# Relayschematic.net
KiCad netlist of a schematic drawn in EAGLE
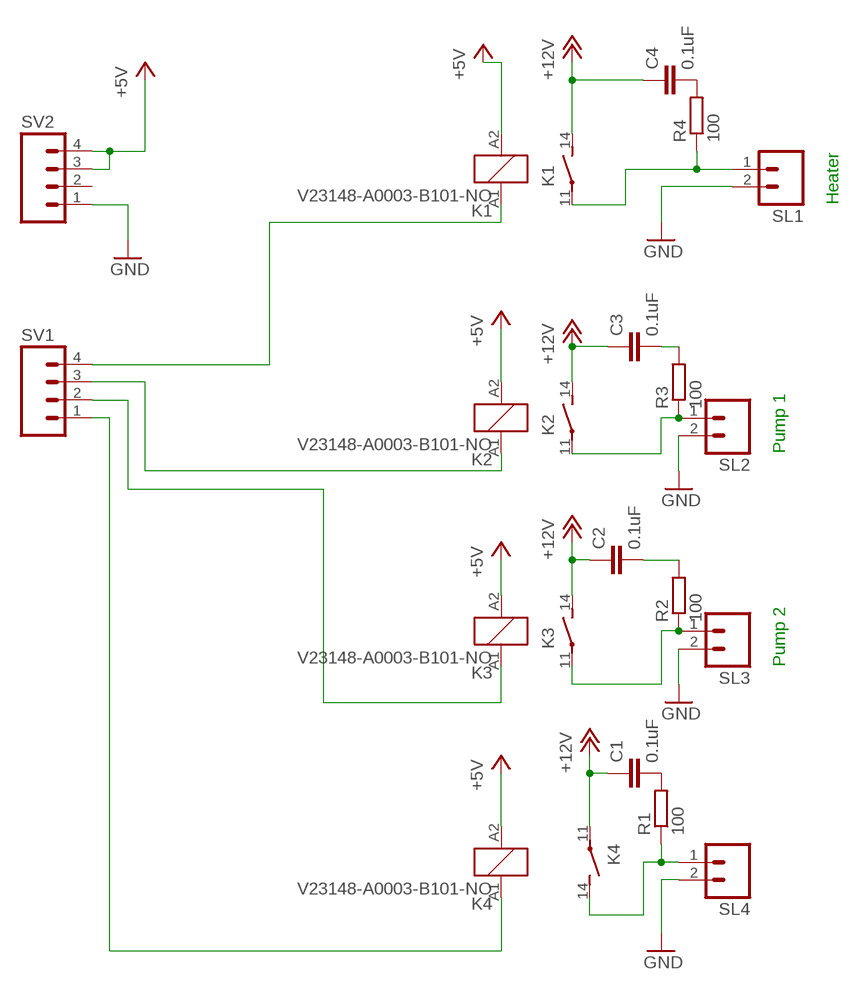
[diagram p0: schematic, sheet 1]

(export (version "E")
  (design (tool "Eeschema 10.0.6"))
  (components
    (comp (ref "C1")
      (value "0.1uF")
      (footprint "eagle-import:C5B2.5")
      (libsource (lib "eagle-import") (part "C5/2.5"))
    )
    (comp (ref "C2")
      (value "0.1uF")
      (footprint "eagle-import:C5B2.5")
      (libsource (lib "eagle-import") (part "C5/2.5"))
    )
    (comp (ref "C3")
      (value "0.1uF")
      (footprint "eagle-import:C5B2.5")
      (libsource (lib "eagle-import") (part "C5/2.5"))
    )
    (comp (ref "C4")
      (value "0.1uF")
      (footprint "eagle-import:C5B2.5")
      (libsource (lib "eagle-import") (part "C5/2.5"))
    )
    (comp (ref "K1")
      (value "V23148-A0003-B101-NO")
      (footprint "eagle-import:V23148-NO")
      (fields (field (name "MPN") "V23148-A0007-A101"))
      (libsource (lib "eagle-import") (part "V23148--NOA0003-B101"))
    )
    (comp (ref "K2")
      (value "V23148-A0003-B101-NO")
      (footprint "eagle-import:V23148-NO")
      (fields (field (name "MPN") "V23148-A0007-A101"))
      (libsource (lib "eagle-import") (part "V23148--NOA0003-B101"))
    )
    (comp (ref "K3")
      (value "V23148-A0003-B101-NO")
      (footprint "eagle-import:V23148-NO")
      (fields (field (name "MPN") "V23148-A0007-A101"))
      (libsource (lib "eagle-import") (part "V23148--NOA0003-B101"))
    )
    (comp (ref "K4")
      (value "V23148-A0003-B101-NO")
      (footprint "eagle-import:V23148-NO")
      (fields (field (name "MPN") "V23148-A0007-A101"))
      (libsource (lib "eagle-import") (part "V23148--NOA0003-B101"))
    )
    (comp (ref "R1")
      (value "100")
      (footprint "eagle-import:0207_10")
      (libsource (lib "eagle-import") (part "R-EU_0207/10"))
    )
    (comp (ref "R2")
      (value "100")
      (footprint "eagle-import:0207_10")
      (libsource (lib "eagle-import") (part "R-EU_0207/10"))
    )
    (comp (ref "R3")
      (value "100")
      (footprint "eagle-import:0207_10")
      (libsource (lib "eagle-import") (part "R-EU_0207/10"))
    )
    (comp (ref "R4")
      (value "100")
      (footprint "eagle-import:0207_10")
      (libsource (lib "eagle-import") (part "R-EU_0207/10"))
    )
    (comp (ref "SL1")
      (value "MA02")
      (footprint "eagle-import:02PA")
      (libsource (lib "eagle-import") (part "MA02"))
    )
    (comp (ref "SL2")
      (value "MA02")
      (footprint "eagle-import:02PA")
      (libsource (lib "eagle-import") (part "MA02"))
    )
    (comp (ref "SL3")
      (value "MA02")
      (footprint "eagle-import:02PA")
      (libsource (lib "eagle-import") (part "MA02"))
    )
    (comp (ref "SL4")
      (value "MA02")
      (footprint "eagle-import:02PA")
      (libsource (lib "eagle-import") (part "MA02"))
    )
    (comp (ref "SV1")
      (value "MA04")
      (footprint "eagle-import:04PA")
      (libsource (lib "eagle-import") (part "MA04"))
    )
    (comp (ref "SV2")
      (value "MA04")
      (footprint "eagle-import:04PA")
      (libsource (lib "eagle-import") (part "MA04"))
    )
  )
  (nets
    (net (code "1") (name "+5V") (class "Default")
      (node (ref "K1") (pin "A2") (pinfunction "2_A2") (pintype "passive"))
      (node (ref "K2") (pin "A2") (pinfunction "2_A2") (pintype "passive"))
      (node (ref "K3") (pin "A2") (pinfunction "2_A2") (pintype "passive"))
      (node (ref "K4") (pin "A2") (pinfunction "2_A2") (pintype "passive"))
      (node (ref "SV2") (pin "3") (pinfunction "3_3") (pintype "passive"))
      (node (ref "SV2") (pin "4") (pinfunction "4_4") (pintype "passive"))
    )
    (net (code "2") (name "+12V") (class "Default")
      (node (ref "C1") (pin "1") (pinfunction "1_1") (pintype "passive"))
      (node (ref "C2") (pin "1") (pinfunction "1_1") (pintype "passive"))
      (node (ref "C3") (pin "1") (pinfunction "1_1") (pintype "passive"))
      (node (ref "C4") (pin "1") (pinfunction "1_1") (pintype "passive"))
      (node (ref "K1") (pin "14") (pinfunction "S_14") (pintype "passive"))
      (node (ref "K2") (pin "14") (pinfunction "S_14") (pintype "passive"))
      (node (ref "K3") (pin "14") (pinfunction "S_14") (pintype "passive"))
      (node (ref "K4") (pin "11") (pinfunction "P_11") (pintype "passive"))
    )
    (net (code "3") (name "GND") (class "Default")
      (node (ref "SL1") (pin "2") (pinfunction "2_2") (pintype "passive"))
      (node (ref "SL2") (pin "2") (pinfunction "2_2") (pintype "passive"))
      (node (ref "SL3") (pin "2") (pinfunction "2_2") (pintype "passive"))
      (node (ref "SL4") (pin "2") (pinfunction "2_2") (pintype "passive"))
      (node (ref "SV2") (pin "1") (pinfunction "1_1") (pintype "passive"))
    )
    (net (code "4") (name "Net-(C1-Pad2)") (class "Default")
      (node (ref "C1") (pin "2") (pinfunction "2_2") (pintype "passive"))
      (node (ref "R1") (pin "2") (pinfunction "2_2") (pintype "passive"))
    )
    (net (code "5") (name "Net-(C2-Pad2)") (class "Default")
      (node (ref "C2") (pin "2") (pinfunction "2_2") (pintype "passive"))
      (node (ref "R2") (pin "2") (pinfunction "2_2") (pintype "passive"))
    )
    (net (code "6") (name "Net-(C3-Pad2)") (class "Default")
      (node (ref "C3") (pin "2") (pinfunction "2_2") (pintype "passive"))
      (node (ref "R3") (pin "2") (pinfunction "2_2") (pintype "passive"))
    )
    (net (code "7") (name "Net-(C4-Pad2)") (class "Default")
      (node (ref "C4") (pin "2") (pinfunction "2_2") (pintype "passive"))
      (node (ref "R4") (pin "2") (pinfunction "2_2") (pintype "passive"))
    )
    (net (code "8") (name "Net-(K1A-1)") (class "Default")
      (node (ref "K1") (pin "A1") (pinfunction "1_A1") (pintype "passive"))
      (node (ref "SV1") (pin "4") (pinfunction "4_4") (pintype "passive"))
    )
    (net (code "9") (name "Net-(K1B-P)") (class "Default")
      (node (ref "K1") (pin "11") (pinfunction "P_11") (pintype "passive"))
      (node (ref "R4") (pin "1") (pinfunction "1_1") (pintype "passive"))
      (node (ref "SL1") (pin "1") (pinfunction "1_1") (pintype "passive"))
    )
    (net (code "10") (name "Net-(K2A-1)") (class "Default")
      (node (ref "K2") (pin "A1") (pinfunction "1_A1") (pintype "passive"))
      (node (ref "SV1") (pin "3") (pinfunction "3_3") (pintype "passive"))
    )
    (net (code "11") (name "Net-(K2B-P)") (class "Default")
      (node (ref "K2") (pin "11") (pinfunction "P_11") (pintype "passive"))
      (node (ref "R3") (pin "1") (pinfunction "1_1") (pintype "passive"))
      (node (ref "SL2") (pin "1") (pinfunction "1_1") (pintype "passive"))
    )
    (net (code "12") (name "Net-(K3A-1)") (class "Default")
      (node (ref "K3") (pin "A1") (pinfunction "1_A1") (pintype "passive"))
      (node (ref "SV1") (pin "2") (pinfunction "2_2") (pintype "passive"))
    )
    (net (code "13") (name "Net-(K3B-P)") (class "Default")
      (node (ref "K3") (pin "11") (pinfunction "P_11") (pintype "passive"))
      (node (ref "R2") (pin "1") (pinfunction "1_1") (pintype "passive"))
      (node (ref "SL3") (pin "1") (pinfunction "1_1") (pintype "passive"))
    )
    (net (code "14") (name "Net-(K4A-1)") (class "Default")
      (node (ref "K4") (pin "A1") (pinfunction "1_A1") (pintype "passive"))
      (node (ref "SV1") (pin "1") (pinfunction "1_1") (pintype "passive"))
    )
    (net (code "15") (name "Net-(K4B-S)") (class "Default")
      (node (ref "K4") (pin "14") (pinfunction "S_14") (pintype "passive"))
      (node (ref "R1") (pin "1") (pinfunction "1_1") (pintype "passive"))
      (node (ref "SL4") (pin "1") (pinfunction "1_1") (pintype "passive"))
    )
    (net (code "16") (name "unconnected-(SV2-Pad2)") (class "Default")
      (node (ref "SV2") (pin "2") (pinfunction "2_2") (pintype "passive"))
    )
  )
)
